# Supply.net
KiCad netlist of a schematic drawn in Altium Designer
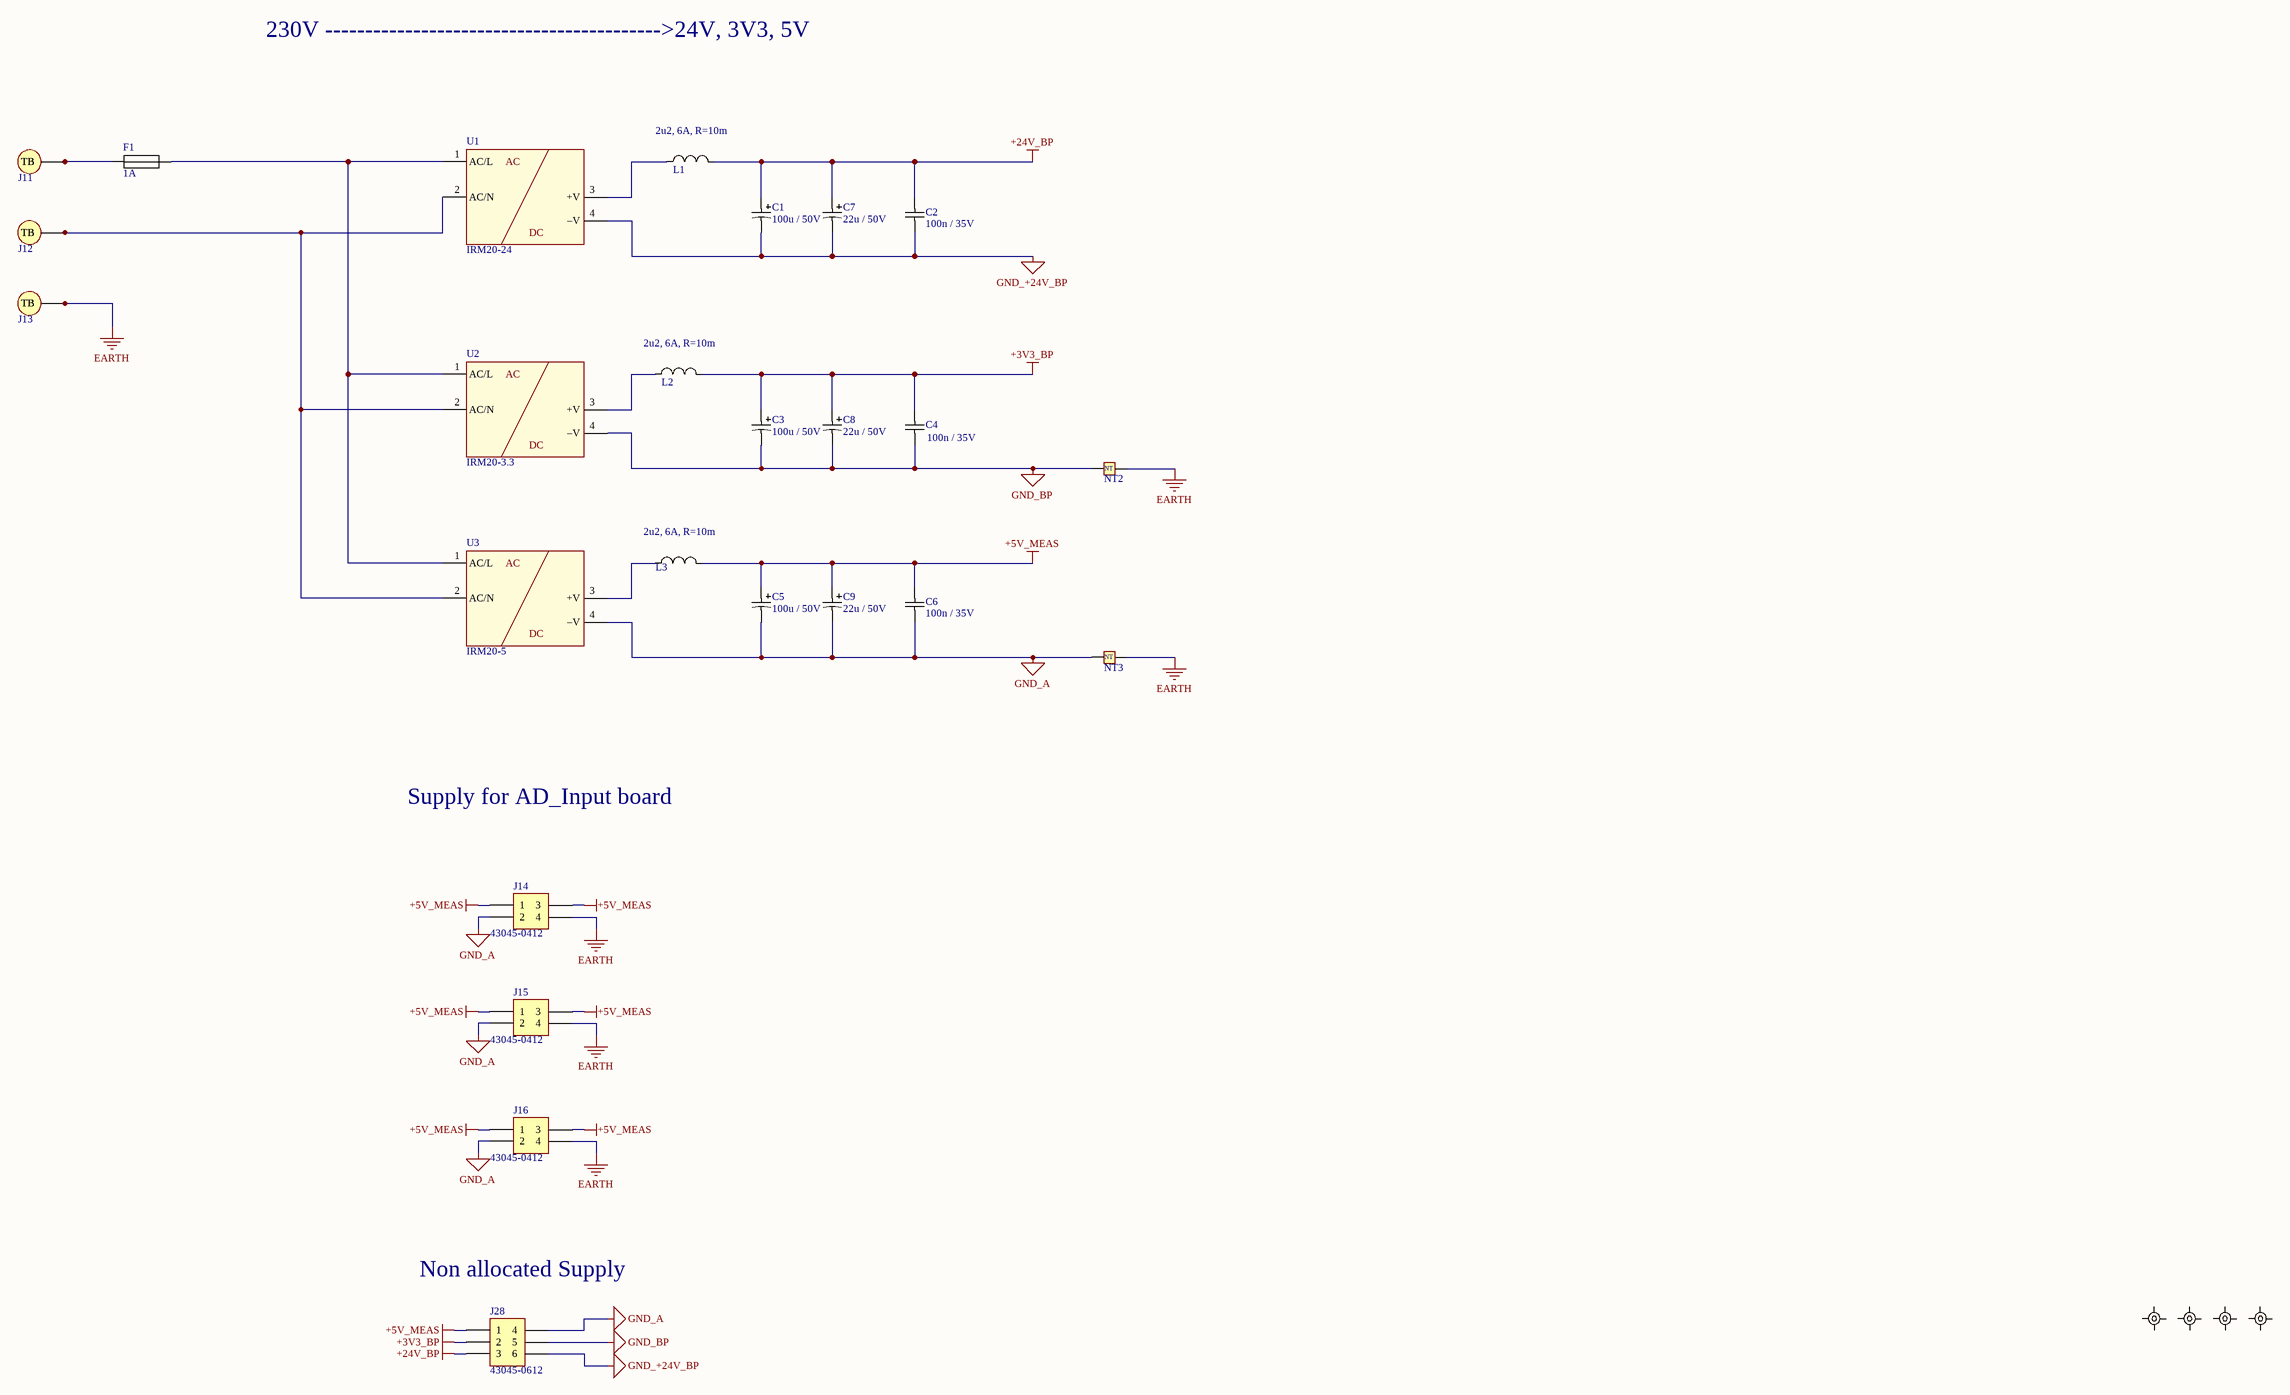
[diagram p0: Supply.SchDoc]

(export (version "E")
  (design (tool "Eeschema 10.0.6"))
  (components
    (comp (ref "C1")
      (value "100u / 50V")
      (footprint "Capacitor POL P3.5 D8.0 H13.0")
      (description "Capacitor polarized")
      (fields (field (name "MANUFACTURER") "Panasonic"))
      (libsource (lib "Capacitor") (part "Capacitor Polarized"))
    )
    (comp (ref "C2")
      (value "100n / 35V")
      (footprint "Capacitor P2.5 C4.5x2.5 H4.0")
      (description "Capacitor")
      (libsource (lib "Capacitor") (part "Capacitor"))
    )
    (comp (ref "C3")
      (value "100u / 50V")
      (footprint "Capacitor POL P3.5 D8.0 H13.0")
      (description "Capacitor polarized")
      (fields (field (name "MANUFACTURER") "Panasonic"))
      (libsource (lib "Capacitor") (part "Capacitor Polarized"))
    )
    (comp (ref "C4")
      (value "100n / 35V")
      (footprint "Capacitor P2.5 C4.5x2.5 H4.0")
      (description "Capacitor")
      (libsource (lib "Capacitor") (part "Capacitor"))
    )
    (comp (ref "C5")
      (value "100u / 50V")
      (footprint "Capacitor POL P3.5 D8.0 H13.0")
      (description "Capacitor polarized")
      (fields (field (name "MANUFACTURER") "Panasonic"))
      (libsource (lib "Capacitor") (part "Capacitor Polarized"))
    )
    (comp (ref "C6")
      (value "100n / 35V")
      (footprint "Capacitor P2.5 C4.5x2.5 H4.0")
      (description "Capacitor")
      (libsource (lib "Capacitor") (part "Capacitor"))
    )
    (comp (ref "C7")
      (value "22u / 50V")
      (footprint "Capacitor POL P2.00 D5.5 H12.0")
      (description "Capacitor polarized")
      (fields (field (name "MANUFACTURER") "Panasonic"))
      (libsource (lib "Capacitor") (part "Capacitor Polarized"))
    )
    (comp (ref "C8")
      (value "22u / 50V")
      (footprint "Capacitor POL P2.00 D5.5 H12.0")
      (description "Capacitor polarized")
      (fields (field (name "MANUFACTURER") "Panasonic"))
      (libsource (lib "Capacitor") (part "Capacitor Polarized"))
    )
    (comp (ref "C9")
      (value "22u / 50V")
      (footprint "Capacitor POL P2.00 D5.5 H12.0")
      (description "Capacitor polarized")
      (fields (field (name "MANUFACTURER") "Panasonic"))
      (libsource (lib "Capacitor") (part "Capacitor Polarized"))
    )
    (comp (ref "F1")
      (value "1A")
      (footprint "Fuse Cartridge 5x20 Shurter")
      (description "Fuse Cartridge 5x20")
      (libsource (lib "Fuse") (part "Fuse Cartridge 5x20"))
    )
    (comp (ref "J11")
      (value "1790351")
      (footprint "PC FFKDSA/H1-7,62 - 1790351")
      (description "Phoenix Contact PCB terminal block - FFKDSA/H1-7,62 - 1790351")
      (libsource (lib "Connector") (part "PC FFKDSA/H1-7,62 - 1790351"))
    )
    (comp (ref "J12")
      (value "1790351")
      (footprint "PC FFKDSA/H1-7,62 - 1790351")
      (description "Phoenix Contact PCB terminal block - FFKDSA/H1-7,62 - 1790351")
      (libsource (lib "Connector") (part "PC FFKDSA/H1-7,62 - 1790351"))
    )
    (comp (ref "J13")
      (value "1790351")
      (footprint "PC FFKDSA/H1-7,62 - 1790351")
      (description "Phoenix Contact PCB terminal block - FFKDSA/H1-7,62 - 1790351")
      (libsource (lib "Connector") (part "PC FFKDSA/H1-7,62 - 1790351"))
    )
    (comp (ref "J14")
      (value "43045-0412")
      (footprint "MOLEX 43045-0412")
      (description "Micro-Fit 3.0 Vertical Header, 3.00mm Pitch, Dual Row, 4 Circuits")
      (fields (field (name "MANUFACTURER") "Molex"))
      (libsource (lib "Connector") (part "MOLEX 43045-0412"))
    )
    (comp (ref "J15")
      (value "43045-0412")
      (footprint "MOLEX 43045-0412")
      (description "Micro-Fit 3.0 Vertical Header, 3.00mm Pitch, Dual Row, 4 Circuits")
      (fields (field (name "MANUFACTURER") "Molex"))
      (libsource (lib "Connector") (part "MOLEX 43045-0412"))
    )
    (comp (ref "J16")
      (value "43045-0412")
      (footprint "MOLEX 43045-0412")
      (description "Micro-Fit 3.0 Vertical Header, 3.00mm Pitch, Dual Row, 4 Circuits")
      (fields (field (name "MANUFACTURER") "Molex"))
      (libsource (lib "Connector") (part "MOLEX 43045-0412"))
    )
    (comp (ref "J28")
      (value "43045-0612")
      (footprint "MOLEX 43045-0612")
      (description "Micro-Fit 3.0 Vertical Header, 3.00mm Pitch, Dual Row, 6 Circuits")
      (fields (field (name "MANUFACTURER") "Molex"))
      (libsource (lib "Connector") (part "MOLEX 43045-0612"))
    )
    (comp (ref "L1")
      (value "2u2, 6A, R=10m")
      (footprint "L P5.0 D10.0 H13.0")
      (description "Inductor")
      (fields (field (name "MANUFACTURER") "Fastron"))
      (libsource (lib "Inductor") (part "Inductor"))
    )
    (comp (ref "L2")
      (value "2u2, 6A, R=10m")
      (footprint "L P5.0 D10.0 H13.0")
      (description "Inductor")
      (fields (field (name "MANUFACTURER") "Fastron"))
      (libsource (lib "Inductor") (part "Inductor"))
    )
    (comp (ref "L3")
      (value "2u2, 6A, R=10m")
      (footprint "L P5.0 D10.0 H13.0")
      (description "Inductor")
      (fields (field (name "MANUFACTURER") "Fastron"))
      (libsource (lib "Inductor") (part "Inductor"))
    )
    (comp (ref "NT2")
      (value "Net Tie")
      (footprint "NET TIE 1005")
      (description "Connection for 2 different NETNAME")
      (libsource (lib "Jumper") (part "Net Tie"))
    )
    (comp (ref "NT3")
      (value "Net Tie")
      (footprint "NET TIE 1005")
      (description "Connection for 2 different NETNAME")
      (libsource (lib "Jumper") (part "Net Tie"))
    )
    (comp (ref "U1")
      (value "IRM20-24")
      (footprint "MEAN WELL IRM-20 Series")
      (description "AC-DC 20W Single Output Encapsulated Type Converter")
      (libsource (lib "VoltageConverter") (part "MEAN WELL IRM-20 series"))
    )
    (comp (ref "U2")
      (value "IRM20-3.3")
      (footprint "MEAN WELL IRM-20 Series")
      (description "AC-DC 20W Single Output Encapsulated Type Converter")
      (libsource (lib "VoltageConverter") (part "MEAN WELL IRM-20 series"))
    )
    (comp (ref "U3")
      (value "IRM20-5")
      (footprint "MEAN WELL IRM-20 Series")
      (description "AC-DC 20W Single Output Encapsulated Type Converter")
      (libsource (lib "VoltageConverter") (part "MEAN WELL IRM-20 series"))
    )
    (comp (ref "Z1")
      (value "1 - 3")
      (footprint "FIDUCIAL")
      (description "FIDUCIAL Din 1mm Dout 3mm")
      (libsource (lib "Mechanic") (part "FIDUCIAL"))
    )
    (comp (ref "Z2")
      (value "1 - 3")
      (footprint "FIDUCIAL")
      (description "FIDUCIAL Din 1mm Dout 3mm")
      (libsource (lib "Mechanic") (part "FIDUCIAL"))
    )
    (comp (ref "Z3")
      (value "1 - 3")
      (footprint "FIDUCIAL")
      (description "FIDUCIAL Din 1mm Dout 3mm")
      (libsource (lib "Mechanic") (part "FIDUCIAL"))
    )
    (comp (ref "Z4")
      (value "1 - 3")
      (footprint "FIDUCIAL")
      (description "FIDUCIAL Din 1mm Dout 3mm")
      (libsource (lib "Mechanic") (part "FIDUCIAL"))
    )
  )
  (nets
    (net (code "1") (name "+3V3_BP") (class "Default")
      (node (ref "C3") (pin "1") (pinfunction "1_1") (pintype "passive"))
      (node (ref "C4") (pin "2") (pinfunction "2_2") (pintype "passive"))
      (node (ref "C8") (pin "1") (pinfunction "1_1") (pintype "passive"))
      (node (ref "J28") (pin "2") (pinfunction "2_2") (pintype "passive"))
      (node (ref "L2") (pin "2") (pinfunction "2_2") (pintype "passive"))
    )
    (net (code "2") (name "+5V_MEAS") (class "Default")
      (node (ref "C5") (pin "1") (pinfunction "1_1") (pintype "passive"))
      (node (ref "C6") (pin "2") (pinfunction "2_2") (pintype "passive"))
      (node (ref "C9") (pin "1") (pinfunction "1_1") (pintype "passive"))
      (node (ref "J14") (pin "1") (pinfunction "1_1") (pintype "passive"))
      (node (ref "J14") (pin "3") (pinfunction "3_3") (pintype "passive"))
      (node (ref "J15") (pin "1") (pinfunction "1_1") (pintype "passive"))
      (node (ref "J15") (pin "3") (pinfunction "3_3") (pintype "passive"))
      (node (ref "J16") (pin "1") (pinfunction "1_1") (pintype "passive"))
      (node (ref "J16") (pin "3") (pinfunction "3_3") (pintype "passive"))
      (node (ref "J28") (pin "1") (pinfunction "1_1") (pintype "passive"))
      (node (ref "L3") (pin "2") (pinfunction "2_2") (pintype "passive"))
    )
    (net (code "3") (name "+24V_BP") (class "Default")
      (node (ref "C1") (pin "1") (pinfunction "1_1") (pintype "passive"))
      (node (ref "C2") (pin "2") (pinfunction "2_2") (pintype "passive"))
      (node (ref "C7") (pin "1") (pinfunction "1_1") (pintype "passive"))
      (node (ref "J28") (pin "3") (pinfunction "3_3") (pintype "passive"))
      (node (ref "L1") (pin "2") (pinfunction "2_2") (pintype "passive"))
    )
    (net (code "4") (name "EARTH") (class "Default")
      (node (ref "J13") (pin "1") (pinfunction "TB_1") (pintype "passive"))
      (node (ref "J13") (pin "2") (pinfunction "TB_2") (pintype "passive"))
      (node (ref "J14") (pin "4") (pinfunction "4_4") (pintype "passive"))
      (node (ref "J15") (pin "4") (pinfunction "4_4") (pintype "passive"))
      (node (ref "J16") (pin "4") (pinfunction "4_4") (pintype "passive"))
      (node (ref "NT2") (pin "2") (pinfunction "2_2") (pintype "passive"))
      (node (ref "NT3") (pin "2") (pinfunction "2_2") (pintype "passive"))
    )
    (net (code "5") (name "GND_+24V_BP") (class "Default")
      (node (ref "C1") (pin "2") (pinfunction "2_2") (pintype "passive"))
      (node (ref "C2") (pin "1") (pinfunction "1_1") (pintype "passive"))
      (node (ref "C7") (pin "2") (pinfunction "2_2") (pintype "passive"))
      (node (ref "J28") (pin "6") (pinfunction "6_6") (pintype "passive"))
      (node (ref "U1") (pin "4") (pinfunction "–V_4") (pintype "passive"))
    )
    (net (code "6") (name "GND_A") (class "Default")
      (node (ref "C5") (pin "2") (pinfunction "2_2") (pintype "passive"))
      (node (ref "C6") (pin "1") (pinfunction "1_1") (pintype "passive"))
      (node (ref "C9") (pin "2") (pinfunction "2_2") (pintype "passive"))
      (node (ref "J14") (pin "2") (pinfunction "2_2") (pintype "passive"))
      (node (ref "J15") (pin "2") (pinfunction "2_2") (pintype "passive"))
      (node (ref "J16") (pin "2") (pinfunction "2_2") (pintype "passive"))
      (node (ref "J28") (pin "4") (pinfunction "4_4") (pintype "passive"))
      (node (ref "NT3") (pin "1") (pinfunction "1_1") (pintype "passive"))
      (node (ref "U3") (pin "4") (pinfunction "–V_4") (pintype "passive"))
    )
    (net (code "7") (name "GND_BP") (class "Default")
      (node (ref "C3") (pin "2") (pinfunction "2_2") (pintype "passive"))
      (node (ref "C4") (pin "1") (pinfunction "1_1") (pintype "passive"))
      (node (ref "C8") (pin "2") (pinfunction "2_2") (pintype "passive"))
      (node (ref "J28") (pin "5") (pinfunction "5_5") (pintype "passive"))
      (node (ref "NT2") (pin "1") (pinfunction "1_1") (pintype "passive"))
      (node (ref "U2") (pin "4") (pinfunction "–V_4") (pintype "passive"))
    )
    (net (code "8") (name "Net-(F1-Pad1)") (class "Default")
      (node (ref "F1") (pin "1") (pinfunction "1_1") (pintype "passive"))
      (node (ref "J11") (pin "1") (pinfunction "TB_1") (pintype "passive"))
      (node (ref "J11") (pin "2") (pinfunction "TB_2") (pintype "passive"))
    )
    (net (code "9") (name "Net-(U1-+V)") (class "Default")
      (node (ref "L1") (pin "1") (pinfunction "1_1") (pintype "passive"))
      (node (ref "U1") (pin "3") (pinfunction "+V_3") (pintype "passive"))
    )
    (net (code "10") (name "Net-(U1-AC{slash}L)") (class "Default")
      (node (ref "F1") (pin "2") (pinfunction "2_2") (pintype "passive"))
      (node (ref "U1") (pin "1") (pinfunction "AC/L_1") (pintype "passive"))
      (node (ref "U2") (pin "1") (pinfunction "AC/L_1") (pintype "passive"))
      (node (ref "U3") (pin "1") (pinfunction "AC/L_1") (pintype "passive"))
    )
    (net (code "11") (name "Net-(U1-AC{slash}N)") (class "Default")
      (node (ref "J12") (pin "1") (pinfunction "TB_1") (pintype "passive"))
      (node (ref "J12") (pin "2") (pinfunction "TB_2") (pintype "passive"))
      (node (ref "U1") (pin "2") (pinfunction "AC/N_2") (pintype "passive"))
      (node (ref "U2") (pin "2") (pinfunction "AC/N_2") (pintype "passive"))
      (node (ref "U3") (pin "2") (pinfunction "AC/N_2") (pintype "passive"))
    )
    (net (code "12") (name "Net-(U2-+V)") (class "Default")
      (node (ref "L2") (pin "1") (pinfunction "1_1") (pintype "passive"))
      (node (ref "U2") (pin "3") (pinfunction "+V_3") (pintype "passive"))
    )
    (net (code "13") (name "Net-(U3-+V)") (class "Default")
      (node (ref "L3") (pin "1") (pinfunction "1_1") (pintype "passive"))
      (node (ref "U3") (pin "3") (pinfunction "+V_3") (pintype "passive"))
    )
  )
)
